# SOM_Codec_WM8731.net
KiCad netlist of a schematic drawn in Altium Designer
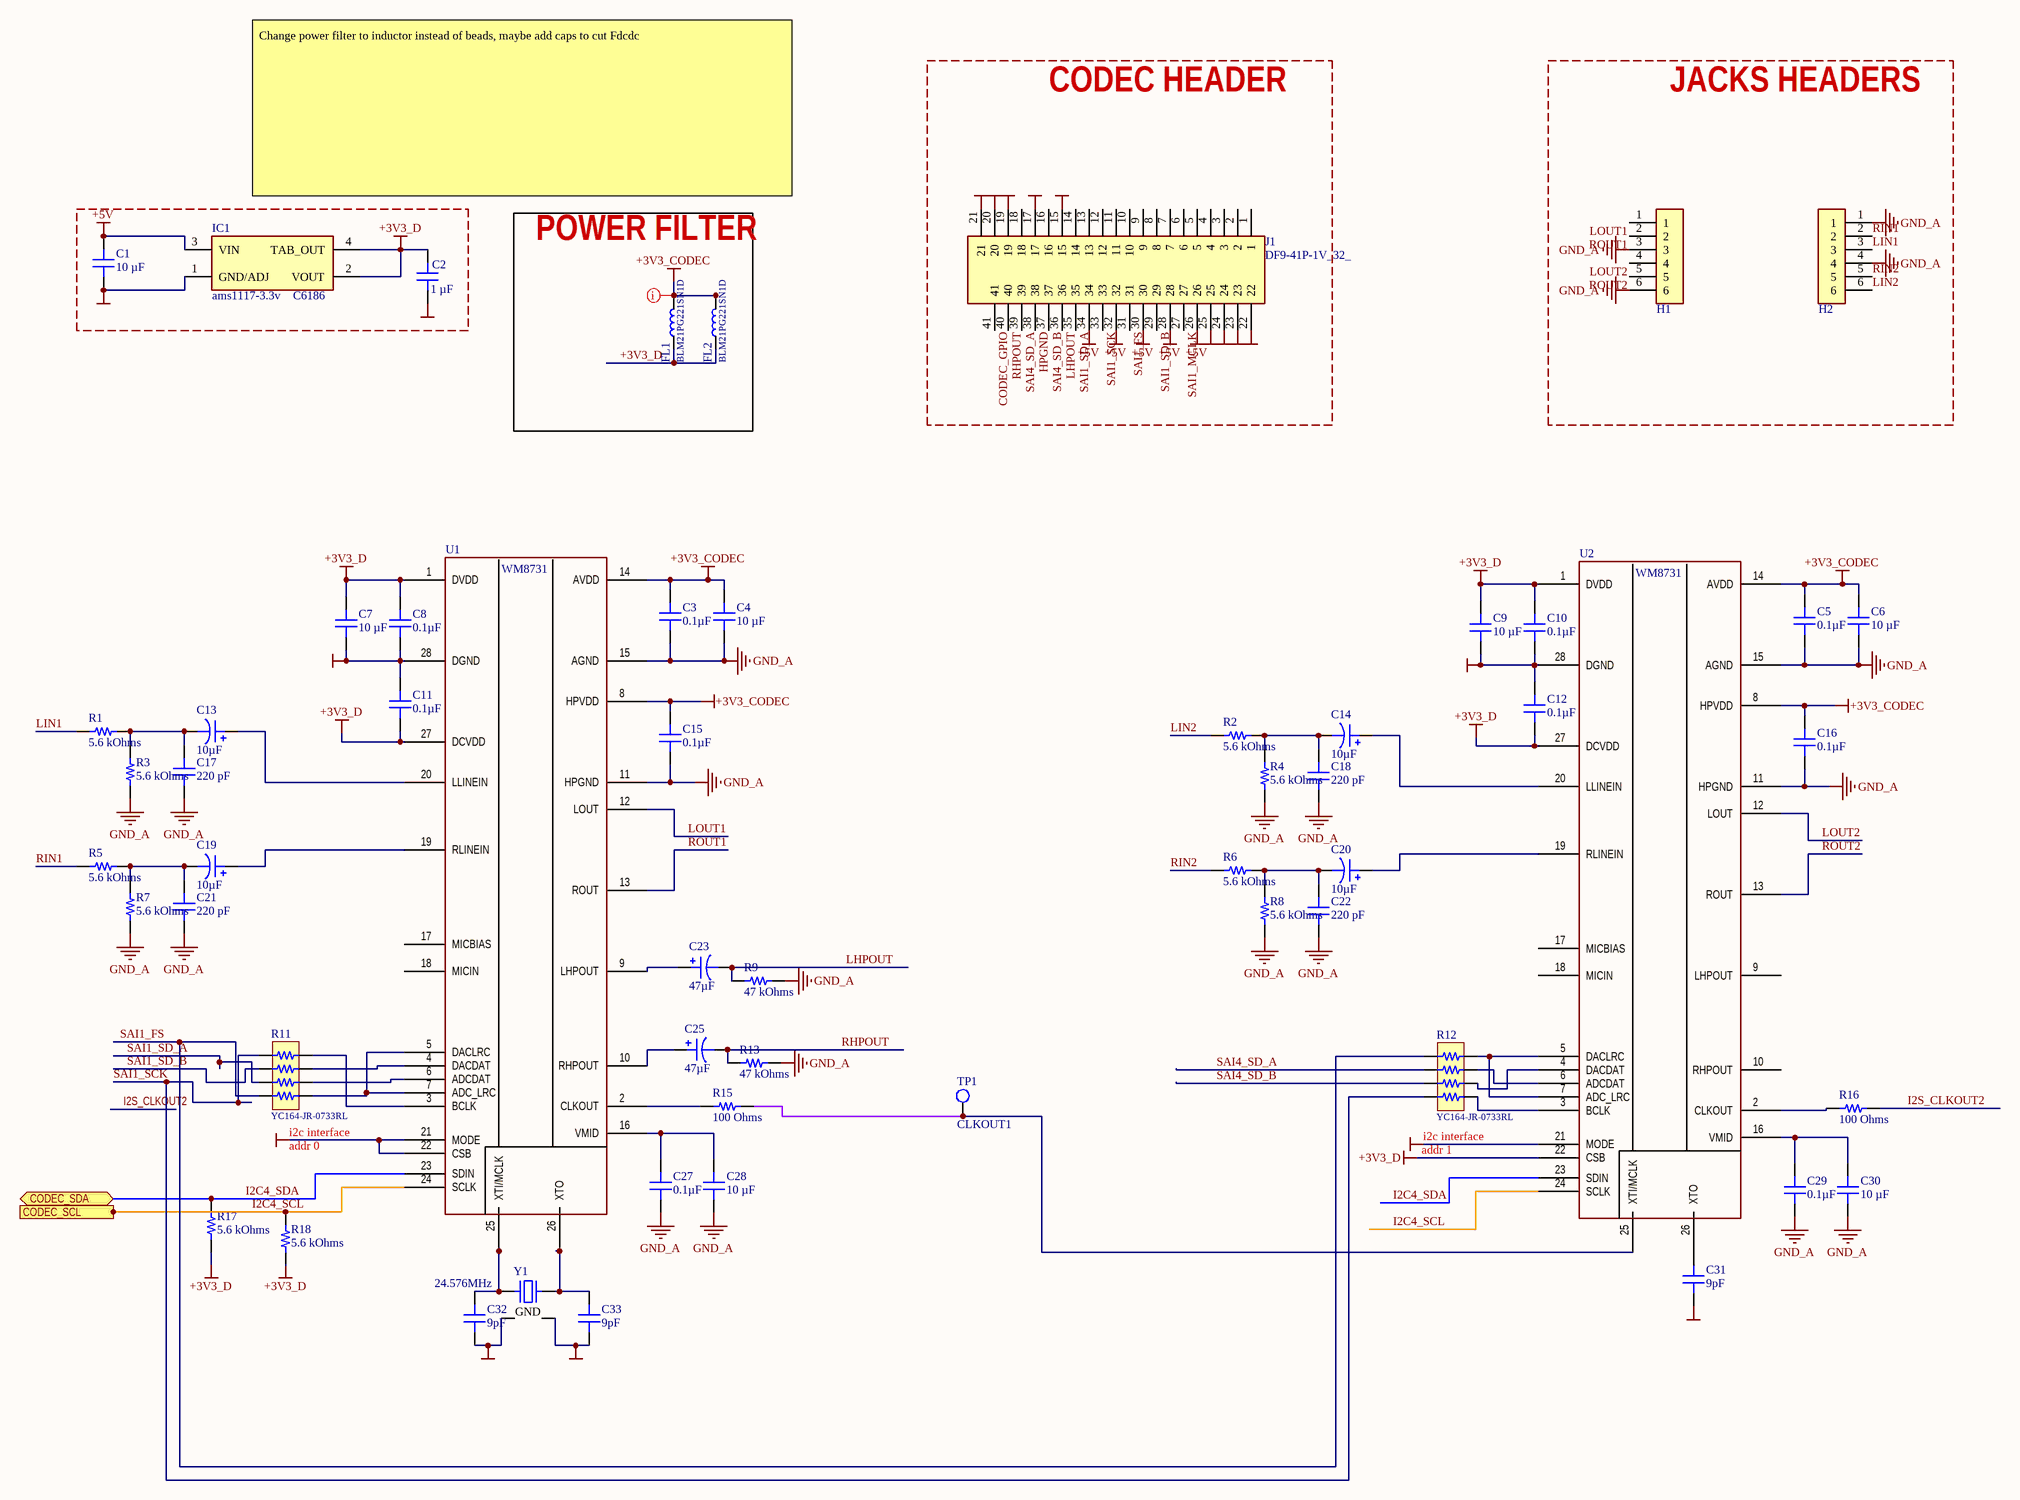
[diagram p0: SOM_Codec_WM8731.SchDoc]

(export (version "E")
  (design (tool "Eeschema 10.0.6"))
  (components
    (comp (ref "C1")
      (value "10 µF")
      (footprint "CAP 0805_2012")
      (description "CAP CER 10UF 10V X5R 0805")
      (fields (field (name "PART NUMBER") "C0805C106K8PAC7800") (field (name "MANUFACTURER") "KEMET"))
      (libsource (lib "Celestial Altium Library - altium_library") (part "Capacitor"))
    )
    (comp (ref "C2")
      (value "1 µF")
      (footprint "CAP 0805_2012")
      (description "CAP CER 1UF 16V X7R 0805")
      (fields (field (name "PART NUMBER") "C0805C105K4RAC7800") (field (name "MANUFACTURER") "KEMET"))
      (libsource (lib "Celestial Altium Library - altium_library") (part "Capacitor"))
    )
    (comp (ref "C3")
      (value "0.1µF")
      (footprint "CAP 0402_1005")
      (description "CAP CER 0.1UF 16V X7R 0402")
      (fields (field (name "PART NUMBER") "C0402C104K4RACAUTO") (field (name "MANUFACTURER") "KEMET"))
      (libsource (lib "Celestial Altium Library - altium_library") (part "Capacitor"))
    )
    (comp (ref "C4")
      (value "10 µF")
      (footprint "CAP 0805_2012")
      (description "CAP CER 10UF 10V X5R 0805")
      (fields (field (name "PART NUMBER") "C0805C106K8PAC7800") (field (name "MANUFACTURER") "KEMET"))
      (libsource (lib "Celestial Altium Library - altium_library") (part "Capacitor"))
    )
    (comp (ref "C5")
      (value "0.1µF")
      (footprint "CAP 0402_1005")
      (description "CAP CER 0.1UF 16V X7R 0402")
      (fields (field (name "PART NUMBER") "C0402C104K4RACAUTO") (field (name "MANUFACTURER") "KEMET"))
      (libsource (lib "Celestial Altium Library - altium_library") (part "Capacitor"))
    )
    (comp (ref "C6")
      (value "10 µF")
      (footprint "CAP 0805_2012")
      (description "CAP CER 10UF 10V X5R 0805")
      (fields (field (name "PART NUMBER") "C0805C106K8PAC7800") (field (name "MANUFACTURER") "KEMET"))
      (libsource (lib "Celestial Altium Library - altium_library") (part "Capacitor"))
    )
    (comp (ref "C7")
      (value "10 µF")
      (footprint "CAP 0805_2012")
      (description "CAP CER 10UF 10V X5R 0805")
      (fields (field (name "PART NUMBER") "C0805C106K8PAC7800") (field (name "MANUFACTURER") "KEMET"))
      (libsource (lib "Celestial Altium Library - altium_library") (part "Capacitor"))
    )
    (comp (ref "C8")
      (value "0.1µF")
      (footprint "CAP 0402_1005")
      (description "CAP CER 0.1UF 16V X7R 0402")
      (fields (field (name "PART NUMBER") "C0402C104K4RACAUTO") (field (name "MANUFACTURER") "KEMET"))
      (libsource (lib "Celestial Altium Library - altium_library") (part "Capacitor"))
    )
    (comp (ref "C9")
      (value "10 µF")
      (footprint "CAP 0805_2012")
      (description "CAP CER 10UF 10V X5R 0805")
      (fields (field (name "PART NUMBER") "C0805C106K8PAC7800") (field (name "MANUFACTURER") "KEMET"))
      (libsource (lib "Celestial Altium Library - altium_library") (part "Capacitor"))
    )
    (comp (ref "C10")
      (value "0.1µF")
      (footprint "CAP 0402_1005")
      (description "CAP CER 0.1UF 16V X7R 0402")
      (fields (field (name "PART NUMBER") "C0402C104K4RACAUTO") (field (name "MANUFACTURER") "KEMET"))
      (libsource (lib "Celestial Altium Library - altium_library") (part "Capacitor"))
    )
    (comp (ref "C11")
      (value "0.1µF")
      (footprint "CAP 0402_1005")
      (description "CAP CER 0.1UF 16V X7R 0402")
      (fields (field (name "PART NUMBER") "C0402C104K4RACAUTO") (field (name "MANUFACTURER") "KEMET"))
      (libsource (lib "Celestial Altium Library - altium_library") (part "Capacitor"))
    )
    (comp (ref "C12")
      (value "0.1µF")
      (footprint "CAP 0402_1005")
      (description "CAP CER 0.1UF 16V X7R 0402")
      (fields (field (name "PART NUMBER") "C0402C104K4RACAUTO") (field (name "MANUFACTURER") "KEMET"))
      (libsource (lib "Celestial Altium Library - altium_library") (part "Capacitor"))
    )
    (comp (ref "C13")
      (value "10µF")
      (footprint "CAP POL 1206_3216")
      (description "CAP TANT 10UF 10% 10V 1206")
      (fields (field (name "PART NUMBER") "T491A106K010AT") (field (name "MANUFACTURER") "KEMET"))
      (libsource (lib "Celestial Altium Library - altium_library") (part "Polarised Capacitor"))
    )
    (comp (ref "C14")
      (value "10µF")
      (footprint "CAP POL 1206_3216")
      (description "CAP TANT 10UF 10% 10V 1206")
      (fields (field (name "PART NUMBER") "T491A106K010AT") (field (name "MANUFACTURER") "KEMET"))
      (libsource (lib "Celestial Altium Library - altium_library") (part "Polarised Capacitor"))
    )
    (comp (ref "C15")
      (value "0.1µF")
      (footprint "CAP 0402_1005")
      (description "CAP CER 0.1UF 16V X7R 0402")
      (fields (field (name "PART NUMBER") "C0402C104K4RACAUTO") (field (name "MANUFACTURER") "KEMET"))
      (libsource (lib "Celestial Altium Library - altium_library") (part "Capacitor"))
    )
    (comp (ref "C16")
      (value "0.1µF")
      (footprint "CAP 0402_1005")
      (description "CAP CER 0.1UF 16V X7R 0402")
      (fields (field (name "PART NUMBER") "C0402C104K4RACAUTO") (field (name "MANUFACTURER") "KEMET"))
      (libsource (lib "Celestial Altium Library - altium_library") (part "Capacitor"))
    )
    (comp (ref "C17")
      (value "220 pF")
      (footprint "CAP 0603_1608")
      (description "CAP CER 220PF 50V X7R 0603")
      (fields (field (name "PART NUMBER") "C0603C221K5RAC7867") (field (name "MANUFACTURER") "KEMET"))
      (libsource (lib "Celestial Altium Library - altium_library") (part "Capacitor"))
    )
    (comp (ref "C18")
      (value "220 pF")
      (footprint "CAP 0603_1608")
      (description "CAP CER 220PF 50V X7R 0603")
      (fields (field (name "PART NUMBER") "C0603C221K5RAC7867") (field (name "MANUFACTURER") "KEMET"))
      (libsource (lib "Celestial Altium Library - altium_library") (part "Capacitor"))
    )
    (comp (ref "C19")
      (value "10µF")
      (footprint "CAP POL 1206_3216")
      (description "CAP TANT 10UF 10% 10V 1206")
      (fields (field (name "PART NUMBER") "T491A106K010AT") (field (name "MANUFACTURER") "KEMET"))
      (libsource (lib "Celestial Altium Library - altium_library") (part "Polarised Capacitor"))
    )
    (comp (ref "C20")
      (value "10µF")
      (footprint "CAP POL 1206_3216")
      (description "CAP TANT 10UF 10% 10V 1206")
      (fields (field (name "PART NUMBER") "T491A106K010AT") (field (name "MANUFACTURER") "KEMET"))
      (libsource (lib "Celestial Altium Library - altium_library") (part "Polarised Capacitor"))
    )
    (comp (ref "C21")
      (value "220 pF")
      (footprint "CAP 0603_1608")
      (description "CAP CER 220PF 50V X7R 0603")
      (fields (field (name "PART NUMBER") "C0603C221K5RAC7867") (field (name "MANUFACTURER") "KEMET"))
      (libsource (lib "Celestial Altium Library - altium_library") (part "Capacitor"))
    )
    (comp (ref "C22")
      (value "220 pF")
      (footprint "CAP 0603_1608")
      (description "CAP CER 220PF 50V X7R 0603")
      (fields (field (name "PART NUMBER") "C0603C221K5RAC7867") (field (name "MANUFACTURER") "KEMET"))
      (libsource (lib "Celestial Altium Library - altium_library") (part "Capacitor"))
    )
    (comp (ref "C23")
      (value "47µF")
      (footprint "CAP POL 2917_7343")
      (description "CAP TANT 47UF 10% 10V 2917")
      (fields (field (name "PART NUMBER") "293D476X9010D2TE3") (field (name "MANUFACTURER") "Vishay Sprague"))
      (libsource (lib "Celestial Altium Library - altium_library") (part "Polarised Capacitor"))
    )
    (comp (ref "C25")
      (value "47µF")
      (footprint "CAP POL 2917_7343")
      (description "CAP TANT 47UF 10% 10V 2917")
      (fields (field (name "PART NUMBER") "293D476X9010D2TE3") (field (name "MANUFACTURER") "Vishay Sprague"))
      (libsource (lib "Celestial Altium Library - altium_library") (part "Polarised Capacitor"))
    )
    (comp (ref "C27")
      (value "0.1µF")
      (footprint "CAP 0402_1005")
      (description "CAP CER 0.1UF 16V X7R 0402")
      (fields (field (name "PART NUMBER") "C0402C104K4RACAUTO") (field (name "MANUFACTURER") "KEMET"))
      (libsource (lib "Celestial Altium Library - altium_library") (part "Capacitor"))
    )
    (comp (ref "C28")
      (value "10 µF")
      (footprint "CAP 0805_2012")
      (description "CAP CER 10UF 10V X5R 0805")
      (fields (field (name "PART NUMBER") "C0805C106K8PAC7800") (field (name "MANUFACTURER") "KEMET"))
      (libsource (lib "Celestial Altium Library - altium_library") (part "Capacitor"))
    )
    (comp (ref "C29")
      (value "0.1µF")
      (footprint "CAP 0402_1005")
      (description "CAP CER 0.1UF 16V X7R 0402")
      (fields (field (name "PART NUMBER") "C0402C104K4RACAUTO") (field (name "MANUFACTURER") "KEMET"))
      (libsource (lib "Celestial Altium Library - altium_library") (part "Capacitor"))
    )
    (comp (ref "C30")
      (value "10 µF")
      (footprint "CAP 0805_2012")
      (description "CAP CER 10UF 10V X5R 0805")
      (fields (field (name "PART NUMBER") "C0805C106K8PAC7800") (field (name "MANUFACTURER") "KEMET"))
      (libsource (lib "Celestial Altium Library - altium_library") (part "Capacitor"))
    )
    (comp (ref "C31")
      (value "9pF")
      (footprint "CAP 0805_2012")
      (description "CAP CER 9PF 250V C0G/NP0 0805")
      (fields (field (name "PART NUMBER") "CBR08C909CAGAC") (field (name "MANUFACTURER") "KEMET"))
      (libsource (lib "Celestial Altium Library - altium_library") (part "Capacitor"))
    )
    (comp (ref "C32")
      (value "9pF")
      (footprint "CAP 0805_2012")
      (description "CAP CER 9PF 250V C0G/NP0 0805")
      (fields (field (name "PART NUMBER") "CBR08C909CAGAC") (field (name "MANUFACTURER") "KEMET"))
      (libsource (lib "Celestial Altium Library - altium_library") (part "Capacitor"))
    )
    (comp (ref "C33")
      (value "9pF")
      (footprint "CAP 0805_2012")
      (description "CAP CER 9PF 250V C0G/NP0 0805")
      (fields (field (name "PART NUMBER") "CBR08C909CAGAC") (field (name "MANUFACTURER") "KEMET"))
      (libsource (lib "Celestial Altium Library - altium_library") (part "Capacitor"))
    )
    (comp (ref "FL1")
      (value "BLM21PG221SN1D")
      (footprint "0805_IND")
      (description "ACM Series 0805 360 Ohm 220mA 500 mOhm DCR 50 V SMT Common Mode Filter")
      (libsource (lib "ProtoStack_H750VBT") (part "BLM21PG221SN1D"))
    )
    (comp (ref "FL2")
      (value "BLM21PG221SN1D")
      (footprint "0805_IND")
      (description "ACM Series 0805 360 Ohm 220mA 500 mOhm DCR 50 V SMT Common Mode Filter")
      (libsource (lib "ProtoStack_H750VBT") (part "BLM21PG221SN1D"))
    )
    (comp (ref "H1")
      (value "1.5-6A")
      (footprint "ProtoStack_H750VBT:1.5-6A")
      (description "Pin Header p=1.5mm, 6 pins")
      (libsource (lib "") (part "1.5-6A_1"))
    )
    (comp (ref "H2")
      (value "1.5-6A")
      (footprint "ProtoStack_H750VBT:1.5-6A")
      (description "Pin Header p=1.5mm, 6 pins")
      (libsource (lib "ProtoStack_H750VBT") (part "1.5-6A"))
    )
    (comp (ref "IC1")
      (value "ams1117-3.3v")
      (footprint "ProtoStack_H750VBT:SOT-223")
      (description "Integrated Circuit")
      (fields (field (name "SUPPLIER PART NUMBER 1") "C6186"))
      (libsource (lib "ProtoStack_H750VBT") (part "ams1117-3.3v"))
    )
    (comp (ref "J1")
      (value "DF9-41P-1V_32_")
      (footprint "HIROSE_DF9-41P-1V(32)")
      (description "Connector")
      (fields
        (field (name "MANUFACTURER_PART_NUMBER") "DF9-41P-1V(32)")
        (field (name "MOUSER PART NUMBER") "798-DF9-41P-1V32")
      )
      (libsource (lib "ProtoStack_H750VBT") (part "DF9-41P-1V_32_"))
    )
    (comp (ref "R1")
      (value "5.6 kOhms")
      (footprint "RES 0603_1608")
      (description "RES SMD 5.6K OHM 0.5% 1/10W 0603")
      (fields (field (name "PART NUMBER") "RT0603DRE075K6L") (field (name "MANUFACTURER") "Yageo"))
      (libsource (lib "Celestial Altium Library - altium_library") (part "Resistor"))
    )
    (comp (ref "R2")
      (value "5.6 kOhms")
      (footprint "RES 0603_1608")
      (description "RES SMD 5.6K OHM 0.5% 1/10W 0603")
      (fields (field (name "PART NUMBER") "RT0603DRE075K6L") (field (name "MANUFACTURER") "Yageo"))
      (libsource (lib "Celestial Altium Library - altium_library") (part "Resistor"))
    )
    (comp (ref "R3")
      (value "5.6 kOhms")
      (footprint "RES 0603_1608")
      (description "RES SMD 5.6K OHM 0.5% 1/10W 0603")
      (fields (field (name "PART NUMBER") "RT0603DRE075K6L") (field (name "MANUFACTURER") "Yageo"))
      (libsource (lib "Celestial Altium Library - altium_library") (part "Resistor"))
    )
    (comp (ref "R4")
      (value "5.6 kOhms")
      (footprint "RES 0603_1608")
      (description "RES SMD 5.6K OHM 0.5% 1/10W 0603")
      (fields (field (name "PART NUMBER") "RT0603DRE075K6L") (field (name "MANUFACTURER") "Yageo"))
      (libsource (lib "Celestial Altium Library - altium_library") (part "Resistor"))
    )
    (comp (ref "R5")
      (value "5.6 kOhms")
      (footprint "RES 0603_1608")
      (description "RES SMD 5.6K OHM 0.5% 1/10W 0603")
      (fields (field (name "PART NUMBER") "RT0603DRE075K6L") (field (name "MANUFACTURER") "Yageo"))
      (libsource (lib "Celestial Altium Library - altium_library") (part "Resistor"))
    )
    (comp (ref "R6")
      (value "5.6 kOhms")
      (footprint "RES 0603_1608")
      (description "RES SMD 5.6K OHM 0.5% 1/10W 0603")
      (fields (field (name "PART NUMBER") "RT0603DRE075K6L") (field (name "MANUFACTURER") "Yageo"))
      (libsource (lib "Celestial Altium Library - altium_library") (part "Resistor"))
    )
    (comp (ref "R7")
      (value "5.6 kOhms")
      (footprint "RES 0603_1608")
      (description "RES SMD 5.6K OHM 0.5% 1/10W 0603")
      (fields (field (name "PART NUMBER") "RT0603DRE075K6L") (field (name "MANUFACTURER") "Yageo"))
      (libsource (lib "Celestial Altium Library - altium_library") (part "Resistor"))
    )
    (comp (ref "R8")
      (value "5.6 kOhms")
      (footprint "RES 0603_1608")
      (description "RES SMD 5.6K OHM 0.5% 1/10W 0603")
      (fields (field (name "PART NUMBER") "RT0603DRE075K6L") (field (name "MANUFACTURER") "Yageo"))
      (libsource (lib "Celestial Altium Library - altium_library") (part "Resistor"))
    )
    (comp (ref "R9")
      (value "47 kOhms")
      (footprint "RES 0603_1608")
      (description "RES SMD 47K OHM 1% 1/10W 0603")
      (fields (field (name "PART NUMBER") "RT0603FRE0747KL") (field (name "MANUFACTURER") "Yageo"))
      (libsource (lib "Celestial Altium Library - altium_library") (part "Resistor"))
    )
    (comp (ref "R11")
      (value "YC164-JR-0733RL")
      (footprint "RESNET 1206-8 CONVEX")
      (description "RES ARRAY 4 RES 33 OHM 1206")
      (fields (field (name "MANUFACTURER") "Yageo") (field (name "TOLERANCE") "±5%"))
      (libsource (lib "Celestial Altium Library - altium_library") (part "Resistor Array (4 circuit)"))
    )
    (comp (ref "R12")
      (value "YC164-JR-0733RL")
      (footprint "RESNET 1206-8 CONVEX")
      (description "RES ARRAY 4 RES 33 OHM 1206")
      (fields (field (name "MANUFACTURER") "Yageo") (field (name "TOLERANCE") "±5%"))
      (libsource (lib "Celestial Altium Library - altium_library") (part "Resistor Array (4 circuit)"))
    )
    (comp (ref "R13")
      (value "47 kOhms")
      (footprint "RES 0603_1608")
      (description "RES SMD 47K OHM 1% 1/10W 0603")
      (fields (field (name "PART NUMBER") "RT0603FRE0747KL") (field (name "MANUFACTURER") "Yageo"))
      (libsource (lib "Celestial Altium Library - altium_library") (part "Resistor"))
    )
    (comp (ref "R15")
      (value "100 Ohms")
      (footprint "RES 0402_1005")
      (description "RES SMD 100 OHM 1% 1/16W 0402")
      (fields (field (name "PART NUMBER") "RT0402FRE07100RL") (field (name "MANUFACTURER") "Yageo"))
      (libsource (lib "Celestial Altium Library - altium_library") (part "Resistor"))
    )
    (comp (ref "R16")
      (value "100 Ohms")
      (footprint "RES 0402_1005")
      (description "RES SMD 100 OHM 1% 1/16W 0402")
      (fields (field (name "PART NUMBER") "RT0402FRE07100RL") (field (name "MANUFACTURER") "Yageo"))
      (libsource (lib "Celestial Altium Library - altium_library") (part "Resistor"))
    )
    (comp (ref "R17")
      (value "5.6 kOhms")
      (footprint "RES 0603_1608")
      (description "RES SMD 5.6K OHM 0.5% 1/10W 0603")
      (fields (field (name "PART NUMBER") "RT0603DRE075K6L") (field (name "MANUFACTURER") "Yageo"))
      (libsource (lib "Celestial Altium Library - altium_library") (part "Resistor"))
    )
    (comp (ref "R18")
      (value "5.6 kOhms")
      (footprint "RES 0603_1608")
      (description "RES SMD 5.6K OHM 0.5% 1/10W 0603")
      (fields (field (name "PART NUMBER") "RT0603DRE075K6L") (field (name "MANUFACTURER") "Yageo"))
      (libsource (lib "Celestial Altium Library - altium_library") (part "Resistor"))
    )
    (comp (ref "TP1")
      (value "CLKOUT1")
      (footprint "TESTPOINT")
      (libsource (lib "DAC_ADC") (part "TestPoint"))
    )
    (comp (ref "U1")
      (value "WM8731")
      (footprint "TSSOP-28")
      (description "Stero in/ot audio codec")
      (libsource (lib "DAC_ADC") (part "WM8731"))
    )
    (comp (ref "U2")
      (value "WM8731")
      (footprint "TSSOP-28")
      (description "Stero in/ot audio codec")
      (libsource (lib "DAC_ADC") (part "WM8731"))
    )
    (comp (ref "Y1")
      (value "24.576MHz")
      (footprint "ABRACON ABM8G")
      (description "CRYSTAL 24.5760MHZ 10PF SMD")
      (fields
        (field (name "PART NUMBER") "ABM8G-24.576MHZ-B4Y-T")
        (field (name "MANUFACTURER") "Abracon LLC")
      )
      (libsource (lib "Celestial Altium Library - altium_library") (part "Abracon Crystal ABM8G"))
    )
  )
  (nets
    (net (code "1") (name "+3V3_CODEC") (class "Default")
      (node (ref "C15") (pin "2") (pinfunction "2_2") (pintype "passive"))
      (node (ref "C16") (pin "2") (pinfunction "2_2") (pintype "passive"))
      (node (ref "C3") (pin "2") (pinfunction "2_2") (pintype "passive"))
      (node (ref "C4") (pin "2") (pinfunction "2_2") (pintype "passive"))
      (node (ref "C5") (pin "2") (pinfunction "2_2") (pintype "passive"))
      (node (ref "C6") (pin "2") (pinfunction "2_2") (pintype "passive"))
      (node (ref "FL1") (pin "2") (pinfunction "2_2") (pintype "passive"))
      (node (ref "FL2") (pin "2") (pinfunction "2_2") (pintype "passive"))
      (node (ref "U1") (pin "14") (pinfunction "AVDD_14") (pintype "passive"))
      (node (ref "U1") (pin "8") (pinfunction "HPVDD_8") (pintype "passive"))
      (node (ref "U2") (pin "14") (pinfunction "AVDD_14") (pintype "passive"))
      (node (ref "U2") (pin "8") (pinfunction "HPVDD_8") (pintype "passive"))
    )
    (net (code "2") (name "+3V3_D") (class "Default")
      (node (ref "C10") (pin "2") (pinfunction "2_2") (pintype "passive"))
      (node (ref "C11") (pin "1") (pinfunction "1_1") (pintype "passive"))
      (node (ref "C12") (pin "1") (pinfunction "1_1") (pintype "passive"))
      (node (ref "C2") (pin "2") (pinfunction "2_2") (pintype "passive"))
      (node (ref "C7") (pin "2") (pinfunction "2_2") (pintype "passive"))
      (node (ref "C8") (pin "2") (pinfunction "2_2") (pintype "passive"))
      (node (ref "C9") (pin "2") (pinfunction "2_2") (pintype "passive"))
      (node (ref "FL1") (pin "1") (pinfunction "1_1") (pintype "passive"))
      (node (ref "FL2") (pin "1") (pinfunction "1_1") (pintype "passive"))
      (node (ref "IC1") (pin "2") (pinfunction "VOUT_2") (pintype "passive"))
      (node (ref "IC1") (pin "4") (pinfunction "TAB_OUT_4") (pintype "passive"))
      (node (ref "R17") (pin "1") (pinfunction "1_1") (pintype "passive"))
      (node (ref "R18") (pin "1") (pinfunction "1_1") (pintype "passive"))
      (node (ref "U1") (pin "1") (pinfunction "DVDD_1") (pintype "passive"))
      (node (ref "U1") (pin "27") (pinfunction "DCVDD_27") (pintype "passive"))
      (node (ref "U2") (pin "1") (pinfunction "DVDD_1") (pintype "passive"))
      (node (ref "U2") (pin "22") (pinfunction "CSB_22") (pintype "passive"))
      (node (ref "U2") (pin "27") (pinfunction "DCVDD_27") (pintype "passive"))
    )
    (net (code "3") (name "+5V") (class "Default")
      (node (ref "C1") (pin "2") (pinfunction "2_2") (pintype "passive"))
      (node (ref "IC1") (pin "3") (pinfunction "VIN_3") (pintype "passive"))
      (node (ref "J1") (pin "26") (pinfunction "26_26") (pintype "passive"))
      (node (ref "J1") (pin "28") (pinfunction "28_28") (pintype "passive"))
      (node (ref "J1") (pin "30") (pinfunction "30_30") (pintype "passive"))
      (node (ref "J1") (pin "32") (pinfunction "32_32") (pintype "passive"))
      (node (ref "J1") (pin "34") (pinfunction "34_34") (pintype "passive"))
    )
    (net (code "4") (name "/CODEC_GPIO") (class "Default")
      (node (ref "J1") (pin "41") (pinfunction "41_41") (pintype "passive"))
    )
    (net (code "5") (name "/HPGND") (class "Default")
      (node (ref "J1") (pin "38") (pinfunction "38_38") (pintype "passive"))
    )
    (net (code "6") (name "/I2C4_SCL") (class "Default")
      (node (ref "R18") (pin "2") (pinfunction "2_2") (pintype "passive"))
      (node (ref "U1") (pin "24") (pinfunction "SCLK_24") (pintype "passive"))
      (node (ref "U2") (pin "24") (pinfunction "SCLK_24") (pintype "passive"))
    )
    (net (code "7") (name "/I2C4_SDA") (class "Default")
      (node (ref "R17") (pin "2") (pinfunction "2_2") (pintype "passive"))
      (node (ref "U1") (pin "23") (pinfunction "SDIN_23") (pintype "passive"))
      (node (ref "U2") (pin "23") (pinfunction "SDIN_23") (pintype "passive"))
    )
    (net (code "8") (name "/I2S_CLKOUT2") (class "Default")
      (node (ref "R16") (pin "2") (pinfunction "2_2") (pintype "passive"))
    )
    (net (code "9") (name "/LHPOUT") (class "Default")
      (node (ref "C23") (pin "2") (pinfunction "2_2") (pintype "passive"))
      (node (ref "J1") (pin "36") (pinfunction "36_36") (pintype "passive"))
      (node (ref "R9") (pin "1") (pinfunction "1_1") (pintype "passive"))
    )
    (net (code "10") (name "/LIN1") (class "Default")
      (node (ref "H2") (pin "3") (pinfunction "3_3") (pintype "passive"))
      (node (ref "R1") (pin "1") (pinfunction "1_1") (pintype "passive"))
    )
    (net (code "11") (name "/LIN2") (class "Default")
      (node (ref "H2") (pin "6") (pinfunction "6_6") (pintype "passive"))
      (node (ref "R2") (pin "1") (pinfunction "1_1") (pintype "passive"))
    )
    (net (code "12") (name "/LOUT1") (class "Default")
      (node (ref "H1") (pin "1") (pinfunction "1_1") (pintype "passive"))
      (node (ref "U1") (pin "12") (pinfunction "LOUT_12") (pintype "passive"))
    )
    (net (code "13") (name "/LOUT2") (class "Default")
      (node (ref "H1") (pin "4") (pinfunction "4_4") (pintype "passive"))
      (node (ref "U2") (pin "12") (pinfunction "LOUT_12") (pintype "passive"))
    )
    (net (code "14") (name "/RHPOUT") (class "Default")
      (node (ref "C25") (pin "2") (pinfunction "2_2") (pintype "passive"))
      (node (ref "J1") (pin "40") (pinfunction "40_40") (pintype "passive"))
      (node (ref "R13") (pin "1") (pinfunction "1_1") (pintype "passive"))
    )
    (net (code "15") (name "/RIN1") (class "Default")
      (node (ref "H2") (pin "2") (pinfunction "2_2") (pintype "passive"))
      (node (ref "R5") (pin "1") (pinfunction "1_1") (pintype "passive"))
    )
    (net (code "16") (name "/RIN2") (class "Default")
      (node (ref "H2") (pin "5") (pinfunction "5_5") (pintype "passive"))
      (node (ref "R6") (pin "1") (pinfunction "1_1") (pintype "passive"))
    )
    (net (code "17") (name "/ROUT1") (class "Default")
      (node (ref "H1") (pin "2") (pinfunction "2_2") (pintype "passive"))
      (node (ref "U1") (pin "13") (pinfunction "ROUT_13") (pintype "passive"))
    )
    (net (code "18") (name "/ROUT2") (class "Default")
      (node (ref "H1") (pin "5") (pinfunction "5_5") (pintype "passive"))
      (node (ref "U2") (pin "13") (pinfunction "ROUT_13") (pintype "passive"))
    )
    (net (code "19") (name "/SAI1_FS") (class "Default")
      (node (ref "J1") (pin "31") (pinfunction "31_31") (pintype "passive"))
      (node (ref "R11") (pin "4") (pinfunction "4_4") (pintype "passive"))
      (node (ref "R12") (pin "1") (pinfunction "1_1") (pintype "passive"))
    )
    (net (code "20") (name "/SAI1_MCLK") (class "Default")
      (node (ref "J1") (pin "27") (pinfunction "27_27") (pintype "passive"))
    )
    (net (code "21") (name "/SAI1_SCK") (class "Default")
      (node (ref "J1") (pin "33") (pinfunction "33_33") (pintype "passive"))
      (node (ref "R11") (pin "1") (pinfunction "1_1") (pintype "passive"))
      (node (ref "R12") (pin "4") (pinfunction "4_4") (pintype "passive"))
    )
    (net (code "22") (name "/SAI1_SD_A") (class "Default")
      (node (ref "J1") (pin "35") (pinfunction "35_35") (pintype "passive"))
      (node (ref "R11") (pin "3") (pinfunction "3_3") (pintype "passive"))
    )
    (net (code "23") (name "/SAI1_SD_B") (class "Default")
      (node (ref "J1") (pin "29") (pinfunction "29_29") (pintype "passive"))
      (node (ref "R11") (pin "2") (pinfunction "2_2") (pintype "passive"))
    )
    (net (code "24") (name "/SAI4_SD_A") (class "Default")
      (node (ref "J1") (pin "39") (pinfunction "39_39") (pintype "passive"))
      (node (ref "R12") (pin "2") (pinfunction "2_2") (pintype "passive"))
    )
    (net (code "25") (name "/SAI4_SD_B") (class "Default")
      (node (ref "J1") (pin "37") (pinfunction "37_37") (pintype "passive"))
      (node (ref "R12") (pin "3") (pinfunction "3_3") (pintype "passive"))
    )
    (net (code "26") (name "GND") (class "Default")
      (node (ref "C1") (pin "1") (pinfunction "1_1") (pintype "passive"))
      (node (ref "C10") (pin "1") (pinfunction "1_1") (pintype "passive"))
      (node (ref "C11") (pin "2") (pinfunction "2_2") (pintype "passive"))
      (node (ref "C12") (pin "2") (pinfunction "2_2") (pintype "passive"))
      (node (ref "C2") (pin "1") (pinfunction "1_1") (pintype "passive"))
      (node (ref "C31") (pin "2") (pinfunction "2_2") (pintype "passive"))
      (node (ref "C32") (pin "2") (pinfunction "2_2") (pintype "passive"))
      (node (ref "C33") (pin "2") (pinfunction "2_2") (pintype "passive"))
      (node (ref "C7") (pin "1") (pinfunction "1_1") (pintype "passive"))
      (node (ref "C8") (pin "1") (pinfunction "1_1") (pintype "passive"))
      (node (ref "C9") (pin "1") (pinfunction "1_1") (pintype "passive"))
      (node (ref "IC1") (pin "1") (pinfunction "GND/ADJ_1") (pintype "passive"))
      (node (ref "J1") (pin "15") (pinfunction "15_15") (pintype "passive"))
      (node (ref "J1") (pin "17") (pinfunction "17_17") (pintype "passive"))
      (node (ref "J1") (pin "19") (pinfunction "19_19") (pintype "passive"))
      (node (ref "J1") (pin "20") (pinfunction "20_20") (pintype "passive"))
      (node (ref "J1") (pin "21") (pinfunction "21_21") (pintype "passive"))
      (node (ref "J1") (pin "22") (pinfunction "22_22") (pintype "passive"))
      (node (ref "J1") (pin "23") (pinfunction "23_23") (pintype "passive"))
      (node (ref "J1") (pin "24") (pinfunction "24_24") (pintype "passive"))
      (node (ref "J1") (pin "25") (pinfunction "25_25") (pintype "passive"))
      (node (ref "U1") (pin "21") (pinfunction "MODE_21") (pintype "passive"))
      (node (ref "U1") (pin "22") (pinfunction "CSB_22") (pintype "passive"))
      (node (ref "U1") (pin "28") (pinfunction "DGND_28") (pintype "passive"))
      (node (ref "U2") (pin "21") (pinfunction "MODE_21") (pintype "passive"))
      (node (ref "U2") (pin "28") (pinfunction "DGND_28") (pintype "passive"))
      (node (ref "Y1") (pin "2") (pinfunction "GND_2") (pintype "passive"))
      (node (ref "Y1") (pin "4") (pinfunction "GND_4") (pintype "passive"))
    )
    (net (code "27") (name "GND_A") (class "Default")
      (node (ref "C15") (pin "1") (pinfunction "1_1") (pintype "passive"))
      (node (ref "C16") (pin "1") (pinfunction "1_1") (pintype "passive"))
      (node (ref "C17") (pin "1") (pinfunction "1_1") (pintype "passive"))
      (node (ref "C18") (pin "1") (pinfunction "1_1") (pintype "passive"))
      (node (ref "C21") (pin "1") (pinfunction "1_1") (pintype "passive"))
      (node (ref "C22") (pin "1") (pinfunction "1_1") (pintype "passive"))
      (node (ref "C27") (pin "2") (pinfunction "2_2") (pintype "passive"))
      (node (ref "C28") (pin "2") (pinfunction "2_2") (pintype "passive"))
      (node (ref "C29") (pin "2") (pinfunction "2_2") (pintype "passive"))
      (node (ref "C3") (pin "1") (pinfunction "1_1") (pintype "passive"))
      (node (ref "C30") (pin "2") (pinfunction "2_2") (pintype "passive"))
      (node (ref "C4") (pin "1") (pinfunction "1_1") (pintype "passive"))
      (node (ref "C5") (pin "1") (pinfunction "1_1") (pintype "passive"))
      (node (ref "C6") (pin "1") (pinfunction "1_1") (pintype "passive"))
      (node (ref "H1") (pin "3") (pinfunction "3_3") (pintype "passive"))
      (node (ref "H1") (pin "6") (pinfunction "6_6") (pintype "passive"))
      (node (ref "H2") (pin "1") (pinfunction "1_1") (pintype "passive"))
      (node (ref "H2") (pin "4") (pinfunction "4_4") (pintype "passive"))
      (node (ref "R13") (pin "2") (pinfunction "2_2") (pintype "passive"))
      (node (ref "R3") (pin "1") (pinfunction "1_1") (pintype "passive"))
      (node (ref "R4") (pin "1") (pinfunction "1_1") (pintype "passive"))
      (node (ref "R7") (pin "1") (pinfunction "1_1") (pintype "passive"))
      (node (ref "R8") (pin "1") (pinfunction "1_1") (pintype "passive"))
      (node (ref "R9") (pin "2") (pinfunction "2_2") (pintype "passive"))
      (node (ref "U1") (pin "11") (pinfunction "HPGND_11") (pintype "passive"))
      (node (ref "U1") (pin "15") (pinfunction "AGND_15") (pintype "passive"))
      (node (ref "U2") (pin "11") (pinfunction "HPGND_11") (pintype "passive"))
      (node (ref "U2") (pin "15") (pinfunction "AGND_15") (pintype "passive"))
    )
    (net (code "28") (name "Net-(C13-Pad2)") (class "Default")
      (node (ref "C13") (pin "2") (pinfunction "2_2") (pintype "passive"))
      (node (ref "C17") (pin "2") (pinfunction "2_2") (pintype "passive"))
      (node (ref "R1") (pin "2") (pinfunction "2_2") (pintype "passive"))
      (node (ref "R3") (pin "2") (pinfunction "2_2") (pintype "passive"))
    )
    (net (code "29") (name "Net-(C14-Pad2)") (class "Default")
      (node (ref "C14") (pin "2") (pinfunction "2_2") (pintype "passive"))
      (node (ref "C18") (pin "2") (pinfunction "2_2") (pintype "passive"))
      (node (ref "R2") (pin "2") (pinfunction "2_2") (pintype "passive"))
      (node (ref "R4") (pin "2") (pinfunction "2_2") (pintype "passive"))
    )
    (net (code "30") (name "Net-(C19-Pad2)") (class "Default")
      (node (ref "C19") (pin "2") (pinfunction "2_2") (pintype "passive"))
      (node (ref "C21") (pin "2") (pinfunction "2_2") (pintype "passive"))
      (node (ref "R5") (pin "2") (pinfunction "2_2") (pintype "passive"))
      (node (ref "R7") (pin "2") (pinfunction "2_2") (pintype "passive"))
    )
    (net (code "31") (name "Net-(C20-Pad2)") (class "Default")
      (node (ref "C20") (pin "2") (pinfunction "2_2") (pintype "passive"))
      (node (ref "C22") (pin "2") (pinfunction "2_2") (pintype "passive"))
      (node (ref "R6") (pin "2") (pinfunction "2_2") (pintype "passive"))
      (node (ref "R8") (pin "2") (pinfunction "2_2") (pintype "passive"))
    )
    (net (code "32") (name "Net-(TP1-12)") (class "Default")
      (node (ref "R15") (pin "2") (pinfunction "2_2") (pintype "passive"))
      (node (ref "TP1") (pin "1") (pinfunction "12_1") (pintype "passive"))
      (node (ref "U2") (pin "25") (pinfunction "XTI/MCLK_25") (pintype "passive"))
    )
    (net (code "33") (name "Net-(U1-ADCDAT)") (class "Default")
      (node (ref "R11") (pin "6") (pinfunction "6_6") (pintype "passive"))
      (node (ref "U1") (pin "6") (pinfunction "ADCDAT_6") (pintype "passive"))
    )
    (net (code "34") (name "Net-(U1-ADC_LRC)") (class "Default")
      (node (ref "R11") (pin "5") (pinfunction "5_5") (pintype "passive"))
      (node (ref "U1") (pin "5") (pinfunction "DACLRC_5") (pintype "passive"))
      (node (ref "U1") (pin "7") (pinfunction "ADC_LRC_7") (pintype "passive"))
    )
    (net (code "35") (name "Net-(U1-BCLK)") (class "Default")
      (node (ref "R11") (pin "8") (pinfunction "8_8") (pintype "passive"))
      (node (ref "U1") (pin "3") (pinfunction "BCLK_3") (pintype "passive"))
    )
    (net (code "36") (name "Net-(U1-CLKOUT)") (class "Default")
      (node (ref "R15") (pin "1") (pinfunction "1_1") (pintype "passive"))
      (node (ref "U1") (pin "2") (pinfunction "CLKOUT_2") (pintype "passive"))
    )
    (net (code "37") (name "Net-(U1-DACDAT)") (class "Default")
      (node (ref "R11") (pin "7") (pinfunction "7_7") (pintype "passive"))
      (node (ref "U1") (pin "4") (pinfunction "DACDAT_4") (pintype "passive"))
    )
    (net (code "38") (name "Net-(U1-LHPOUT)") (class "Default")
      (node (ref "C23") (pin "1") (pinfunction "1_1") (pintype "passive"))
      (node (ref "U1") (pin "9") (pinfunction "LHPOUT_9") (pintype "passive"))
    )
    (net (code "39") (name "Net-(U1-LLINEIN)") (class "Default")
      (node (ref "C13") (pin "1") (pinfunction "1_1") (pintype "passive"))
      (node (ref "U1") (pin "20") (pinfunction "LLINEIN_20") (pintype "passive"))
    )
    (net (code "40") (name "Net-(U1-RHPOUT)") (class "Default")
      (node (ref "C25") (pin "1") (pinfunction "1_1") (pintype "passive"))
      (node (ref "U1") (pin "10") (pinfunction "RHPOUT_10") (pintype "passive"))
    )
    (net (code "41") (name "Net-(U1-RLINEIN)") (class "Default")
      (node (ref "C19") (pin "1") (pinfunction "1_1") (pintype "passive"))
      (node (ref "U1") (pin "19") (pinfunction "RLINEIN_19") (pintype "passive"))
    )
    (net (code "42") (name "Net-(U1-VMID)") (class "Default")
      (node (ref "C27") (pin "1") (pinfunction "1_1") (pintype "passive"))
      (node (ref "C28") (pin "1") (pinfunction "1_1") (pintype "passive"))
      (node (ref "U1") (pin "16") (pinfunction "VMID_16") (pintype "passive"))
    )
    (net (code "43") (name "Net-(U1-XTI{slash}MCLK)") (class "Default")
      (node (ref "C32") (pin "1") (pinfunction "1_1") (pintype "passive"))
      (node (ref "U1") (pin "25") (pinfunction "XTI/MCLK_25") (pintype "passive"))
      (node (ref "Y1") (pin "1") (pinfunction "1_1") (pintype "passive"))
    )
    (net (code "44") (name "Net-(U1-XTO)") (class "Default")
      (node (ref "C33") (pin "1") (pinfunction "1_1") (pintype "passive"))
      (node (ref "U1") (pin "26") (pinfunction "XTO_26") (pintype "passive"))
      (node (ref "Y1") (pin "3") (pinfunction "3_3") (pintype "passive"))
    )
    (net (code "45") (name "Net-(U2-ADCDAT)") (class "Default")
      (node (ref "R12") (pin "7") (pinfunction "7_7") (pintype "passive"))
      (node (ref "U2") (pin "6") (pinfunction "ADCDAT_6") (pintype "passive"))
    )
    (net (code "46") (name "Net-(U2-ADC_LRC)") (class "Default")
      (node (ref "R12") (pin "8") (pinfunction "8_8") (pintype "passive"))
      (node (ref "U2") (pin "5") (pinfunction "DACLRC_5") (pintype "passive"))
      (node (ref "U2") (pin "7") (pinfunction "ADC_LRC_7") (pintype "passive"))
    )
    (net (code "47") (name "Net-(U2-BCLK)") (class "Default")
      (node (ref "R12") (pin "5") (pinfunction "5_5") (pintype "passive"))
      (node (ref "U2") (pin "3") (pinfunction "BCLK_3") (pintype "passive"))
    )
    (net (code "48") (name "Net-(U2-CLKOUT)") (class "Default")
      (node (ref "R16") (pin "1") (pinfunction "1_1") (pintype "passive"))
      (node (ref "U2") (pin "2") (pinfunction "CLKOUT_2") (pintype "passive"))
    )
    (net (code "49") (name "Net-(U2-DACDAT)") (class "Default")
      (node (ref "R12") (pin "6") (pinfunction "6_6") (pintype "passive"))
      (node (ref "U2") (pin "4") (pinfunction "DACDAT_4") (pintype "passive"))
    )
    (net (code "50") (name "Net-(U2-LLINEIN)") (class "Default")
      (node (ref "C14") (pin "1") (pinfunction "1_1") (pintype "passive"))
      (node (ref "U2") (pin "20") (pinfunction "LLINEIN_20") (pintype "passive"))
    )
    (net (code "51") (name "Net-(U2-RLINEIN)") (class "Default")
      (node (ref "C20") (pin "1") (pinfunction "1_1") (pintype "passive"))
      (node (ref "U2") (pin "19") (pinfunction "RLINEIN_19") (pintype "passive"))
    )
    (net (code "52") (name "Net-(U2-VMID)") (class "Default")
      (node (ref "C29") (pin "1") (pinfunction "1_1") (pintype "passive"))
      (node (ref "C30") (pin "1") (pinfunction "1_1") (pintype "passive"))
      (node (ref "U2") (pin "16") (pinfunction "VMID_16") (pintype "passive"))
    )
    (net (code "53") (name "Net-(U2-XTO)") (class "Default")
      (node (ref "C31") (pin "1") (pinfunction "1_1") (pintype "passive"))
      (node (ref "U2") (pin "26") (pinfunction "XTO_26") (pintype "passive"))
    )
    (net (code "54") (name "unconnected-(J1-Pad1)") (class "Default")
      (node (ref "J1") (pin "1") (pinfunction "1_1") (pintype "passive"))
    )
    (net (code "55") (name "unconnected-(J1-Pad2)") (class "Default")
      (node (ref "J1") (pin "2") (pinfunction "2_2") (pintype "passive"))
    )
    (net (code "56") (name "unconnected-(J1-Pad3)") (class "Default")
      (node (ref "J1") (pin "3") (pinfunction "3_3") (pintype "passive"))
    )
    (net (code "57") (name "unconnected-(J1-Pad4)") (class "Default")
      (node (ref "J1") (pin "4") (pinfunction "4_4") (pintype "passive"))
    )
    (net (code "58") (name "unconnected-(J1-Pad5)") (class "Default")
      (node (ref "J1") (pin "5") (pinfunction "5_5") (pintype "passive"))
    )
    (net (code "59") (name "unconnected-(J1-Pad6)") (class "Default")
      (node (ref "J1") (pin "6") (pinfunction "6_6") (pintype "passive"))
    )
    (net (code "60") (name "unconnected-(J1-Pad7)") (class "Default")
      (node (ref "J1") (pin "7") (pinfunction "7_7") (pintype "passive"))
    )
    (net (code "61") (name "unconnected-(J1-Pad8)") (class "Default")
      (node (ref "J1") (pin "8") (pinfunction "8_8") (pintype "passive"))
    )
    (net (code "62") (name "unconnected-(J1-Pad9)") (class "Default")
      (node (ref "J1") (pin "9") (pinfunction "9_9") (pintype "passive"))
    )
    (net (code "63") (name "unconnected-(J1-Pad10)") (class "Default")
      (node (ref "J1") (pin "10") (pinfunction "10_10") (pintype "passive"))
    )
    (net (code "64") (name "unconnected-(J1-Pad11)") (class "Default")
      (node (ref "J1") (pin "11") (pinfunction "11_11") (pintype "passive"))
    )
    (net (code "65") (name "unconnected-(J1-Pad12)") (class "Default")
      (node (ref "J1") (pin "12") (pinfunction "12_12") (pintype "passive"))
    )
    (net (code "66") (name "unconnected-(J1-Pad13)") (class "Default")
      (node (ref "J1") (pin "13") (pinfunction "13_13") (pintype "passive"))
    )
    (net (code "67") (name "unconnected-(J1-Pad14)") (class "Default")
      (node (ref "J1") (pin "14") (pinfunction "14_14") (pintype "passive"))
    )
    (net (code "68") (name "unconnected-(J1-Pad16)") (class "Default")
      (node (ref "J1") (pin "16") (pinfunction "16_16") (pintype "passive"))
    )
    (net (code "69") (name "unconnected-(J1-Pad18)") (class "Default")
      (node (ref "J1") (pin "18") (pinfunction "18_18") (pintype "passive"))
    )
    (net (code "70") (name "unconnected-(U1-MICBIAS-Pad17)") (class "Default")
      (node (ref "U1") (pin "17") (pinfunction "MICBIAS_17") (pintype "passive"))
    )
    (net (code "71") (name "unconnected-(U1-MICIN-Pad18)") (class "Default")
      (node (ref "U1") (pin "18") (pinfunction "MICIN_18") (pintype "passive"))
    )
    (net (code "72") (name "unconnected-(U2-LHPOUT-Pad9)") (class "Default")
      (node (ref "U2") (pin "9") (pinfunction "LHPOUT_9") (pintype "passive"))
    )
    (net (code "73") (name "unconnected-(U2-MICBIAS-Pad17)") (class "Default")
      (node (ref "U2") (pin "17") (pinfunction "MICBIAS_17") (pintype "passive"))
    )
    (net (code "74") (name "unconnected-(U2-MICIN-Pad18)") (class "Default")
      (node (ref "U2") (pin "18") (pinfunction "MICIN_18") (pintype "passive"))
    )
    (net (code "75") (name "unconnected-(U2-RHPOUT-Pad10)") (class "Default")
      (node (ref "U2") (pin "10") (pinfunction "RHPOUT_10") (pintype "passive"))
    )
  )
)
